# SAM4N_Xplained_Pro_EDBG.net
KiCad netlist of a schematic drawn in Altium Designer
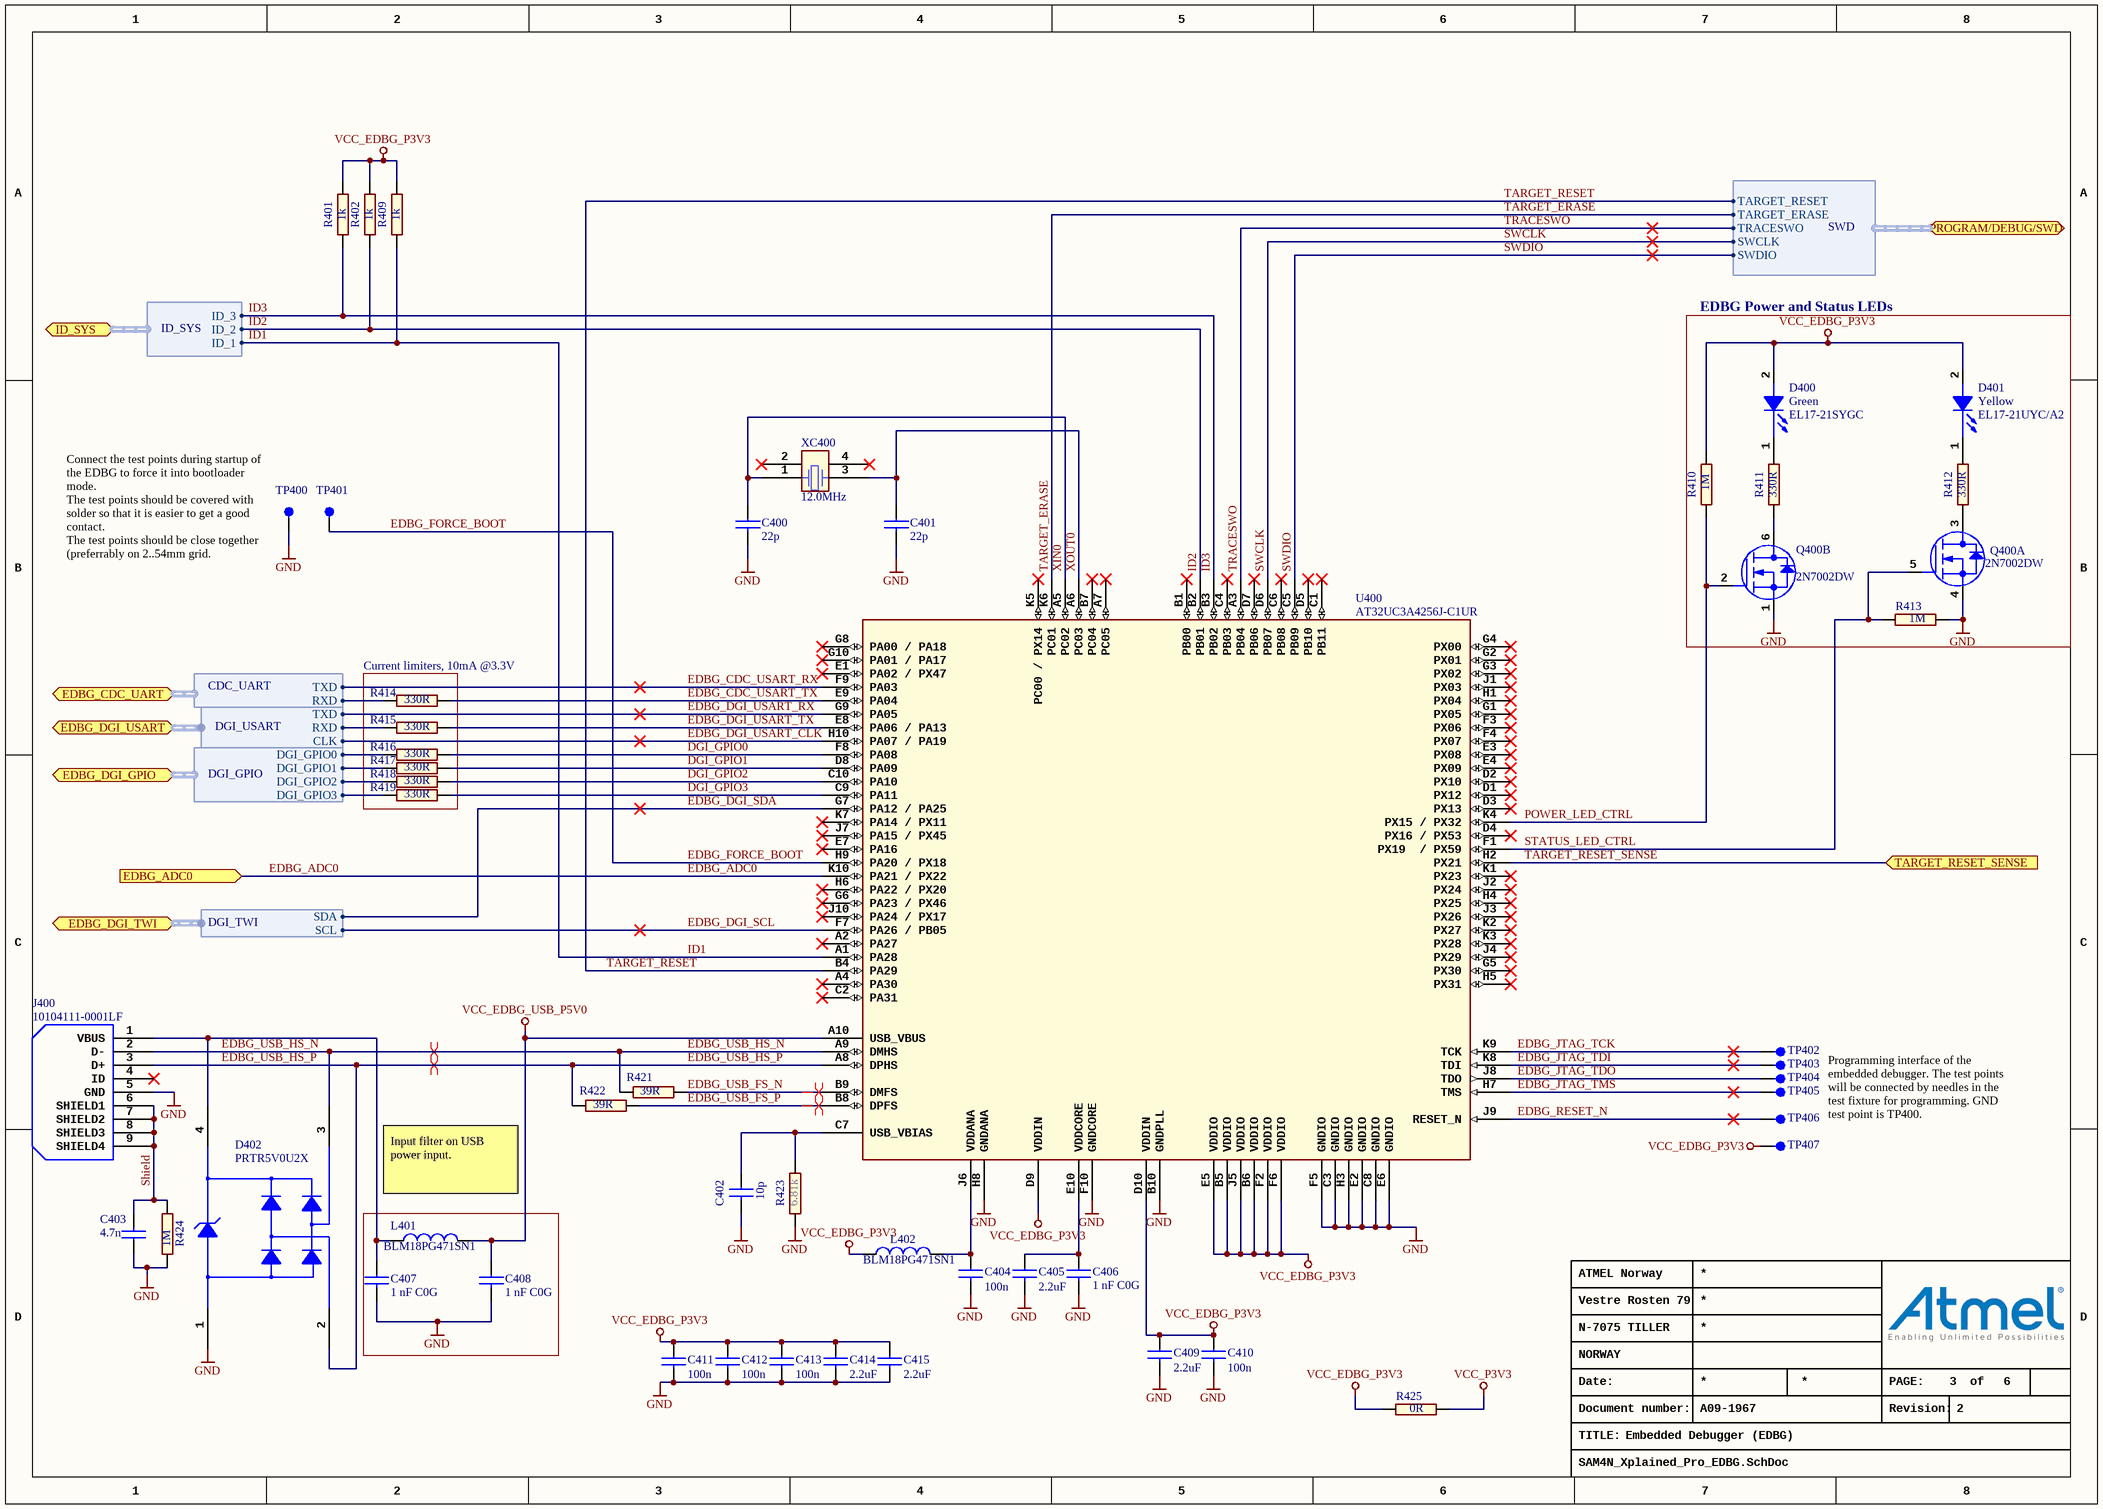
[diagram p0: SAM4N_Xplained_Pro_EDBG.SchDoc]

(export (version "E")
  (design (tool "Eeschema 10.0.6"))
  (components
    (comp (ref "C400")
      (value "22p")
      (footprint "AP1-00053")
      (description "Ceramic capacitor, SMD 0402, NP0, 50V, +/-5%")
      (fields (field (name "TOLERANCE") "50V, +/-5%"))
      (libsource (lib "AltiumDbLib") (part "CAP-NONPOL"))
    )
    (comp (ref "C401")
      (value "22p")
      (footprint "AP1-00053")
      (description "Ceramic capacitor, SMD 0402, NP0, 50V, +/-5%")
      (fields (field (name "TOLERANCE") "50V, +/-5%"))
      (libsource (lib "AltiumDbLib") (part "CAP-NONPOL"))
    )
    (comp (ref "C402")
      (value "10p")
      (footprint "AP1-00053")
      (description "Ceramic capacitor, SMD 0402, NP0, 50V, +/-5%")
      (fields (field (name "TOLERANCE") "50V, +/-5%"))
      (libsource (lib "AltiumDbLib") (part "CAP-NONPOL"))
    )
    (comp (ref "C403")
      (value "4.7n")
      (footprint "AP1-00053")
      (description "Ceramic capacitor, SMD 0402, X7R, 25V, +/-10%")
      (fields (field (name "TOLERANCE") "25V, +/-10%") (field (name "Comment") "CAP-NONPOL"))
      (libsource (lib "AltiumDbLib") (part "CAP-NONPOL"))
    )
    (comp (ref "C404")
      (value "100n")
      (footprint "AP1-00053")
      (description "Ceramic capacitor, SMD 0402, X7R, 16V, +/-10%")
      (fields (field (name "TOLERANCE") "16V, +/-10%") (field (name "MANUFACTURER") "Kemet"))
      (libsource (lib "AltiumDbLib") (part "CAP-NONPOL"))
    )
    (comp (ref "C405")
      (value "2.2uF")
      (footprint "AP1-00053")
      (description "Ceramic capacitor, SMD 0402, X5R, 6.3V, +/-20%")
      (fields (field (name "TOLERANCE") "±20%") (field (name "MANUFACTURER") "Kemet"))
      (libsource (lib "AltiumDbLib") (part "CAP-NONPOL"))
    )
    (comp (ref "C406")
      (value "1 nF C0G")
      (footprint "AP1-00053")
      (description "Ceramic capacitor, SMD 0402, C0G, 50V, +/-5%")
      (fields (field (name "TOLERANCE") "5%") (field (name "MANUFACTURER") "Murata"))
      (libsource (lib "AltiumDbLib") (part "CAP-NONPOL"))
    )
    (comp (ref "C407")
      (value "1 nF C0G")
      (footprint "AP1-00053")
      (description "Ceramic capacitor, SMD 0402, C0G, 50V, +/-5%")
      (fields (field (name "TOLERANCE") "5%") (field (name "MANUFACTURER") "Murata"))
      (libsource (lib "AltiumDbLib") (part "CAP-NONPOL"))
    )
    (comp (ref "C408")
      (value "1 nF C0G")
      (footprint "AP1-00053")
      (description "Ceramic capacitor, SMD 0402, C0G, 50V, +/-5%")
      (fields (field (name "TOLERANCE") "5%") (field (name "MANUFACTURER") "Murata"))
      (libsource (lib "AltiumDbLib") (part "CAP-NONPOL"))
    )
    (comp (ref "C409")
      (value "2.2uF")
      (footprint "AP1-00053")
      (description "Ceramic capacitor, SMD 0402, X5R, 6.3V, +/-20%")
      (fields (field (name "TOLERANCE") "±20%") (field (name "MANUFACTURER") "Kemet"))
      (libsource (lib "AltiumDbLib") (part "CAP-NONPOL"))
    )
    (comp (ref "C410")
      (value "100n")
      (footprint "AP1-00053")
      (description "Ceramic capacitor, SMD 0402, X7R, 16V, +/-10%")
      (fields (field (name "TOLERANCE") "16V, +/-10%") (field (name "MANUFACTURER") "Kemet"))
      (libsource (lib "AltiumDbLib") (part "CAP-NONPOL"))
    )
    (comp (ref "C411")
      (value "100n")
      (footprint "AP1-00053")
      (description "Ceramic capacitor, SMD 0402, X7R, 16V, +/-10%")
      (fields (field (name "TOLERANCE") "16V, +/-10%") (field (name "MANUFACTURER") "Kemet"))
      (libsource (lib "AltiumDbLib") (part "CAP-NONPOL"))
    )
    (comp (ref "C412")
      (value "100n")
      (footprint "AP1-00053")
      (description "Ceramic capacitor, SMD 0402, X7R, 16V, +/-10%")
      (fields (field (name "TOLERANCE") "16V, +/-10%") (field (name "MANUFACTURER") "Kemet"))
      (libsource (lib "AltiumDbLib") (part "CAP-NONPOL"))
    )
    (comp (ref "C413")
      (value "100n")
      (footprint "AP1-00053")
      (description "Ceramic capacitor, SMD 0402, X7R, 16V, +/-10%")
      (fields (field (name "TOLERANCE") "16V, +/-10%") (field (name "MANUFACTURER") "Kemet"))
      (libsource (lib "AltiumDbLib") (part "CAP-NONPOL"))
    )
    (comp (ref "C414")
      (value "2.2uF")
      (footprint "AP1-00053")
      (description "Ceramic capacitor, SMD 0402, X5R, 6.3V, +/-20%")
      (fields (field (name "TOLERANCE") "±20%") (field (name "MANUFACTURER") "Kemet"))
      (libsource (lib "AltiumDbLib") (part "CAP-NONPOL"))
    )
    (comp (ref "C415")
      (value "2.2uF")
      (footprint "AP1-00053")
      (description "Ceramic capacitor, SMD 0402, X5R, 6.3V, +/-20%")
      (fields (field (name "TOLERANCE") "±20%") (field (name "MANUFACTURER") "Kemet"))
      (libsource (lib "AltiumDbLib") (part "CAP-NONPOL"))
    )
    (comp (ref "D400")
      (value "Green")
      (footprint "AP4-00013")
      (description "LED, Green, Wave length=575nm, SMD 0805, ±70°")
      (fields
        (field (name "ALTIUM_VALUE") "EL17-21SYGC")
        (field (name "MANUFACTURER") "Everlight")
        (field (name "MPN") "EL17-21SYGC")
      )
      (libsource (lib "AltiumDbLib") (part "LED_12"))
    )
    (comp (ref "D401")
      (value "Yellow")
      (footprint "AP4-00013")
      (description "LED, Yellow, Wave length=591nm, SMD 0805, ±70°")
      (fields
        (field (name "ALTIUM_VALUE") "EL17-21UYC/A2")
        (field (name "MANUFACTURER") "Everlight")
        (field (name "MPN") "17-21UYC/S530-A3/TR8")
      )
      (libsource (lib "AltiumDbLib") (part "LED_12"))
    )
    (comp (ref "D402")
      (value "PRTR5V0U2X")
      (footprint "AP4-00001")
      (description "Double rail-to-rail USB ESD protection diode")
      (fields (field (name "MANUFACTURER") "Philips"))
      (libsource (lib "AltiumDbLib") (part "PRTR5V0U2X"))
    )
    (comp (ref "J400")
      (value "10104111-0001LF")
      (footprint "AP8-00604")
      (description "Micro USB AB Connector")
      (fields (field (name "MANUFACTURER") "FCI") (field (name "Comment") "USB_AB"))
      (libsource (lib "AltiumDbLib") (part "USB_AB"))
    )
    (comp (ref "L401")
      (value "BLM18PG471SN1")
      (footprint "AP3-00005")
      (description "SMD RF inductor 0603. Z=470Ohm (@100MHz), Max R(dc)=0.65Ohm, Max current=1A")
      (fields (field (name "TOLERANCE") "±25%") (field (name "MANUFACTURER") "Murata"))
      (libsource (lib "AltiumDbLib") (part "INDUCTOR"))
    )
    (comp (ref "L402")
      (value "BLM18PG471SN1")
      (footprint "AP3-00005")
      (description "SMD RF inductor 0603. Z=470Ohm (@100MHz), Max R(dc)=0.65Ohm, Max current=1A")
      (fields (field (name "TOLERANCE") "±25%") (field (name "MANUFACTURER") "Murata"))
      (libsource (lib "AltiumDbLib") (part "INDUCTOR"))
    )
    (comp (ref "Q400")
      (value "2N7002DW")
      (footprint "AP5-00001")
      (description "Dual N-Channel MOSFET, 60V, 115mA cont,RDS(ON) < 7.5 Ohm @50mA@5V, SOT-363")
      (fields
        (field (name "MANUFACTURER") "Fairchild")
        (field (name "Comment") "Same as 2N7002 but with two MOSFETs in one package")
      )
      (libsource (lib "AltiumDbLib") (part "MOSFET_DUAL_N_S2G2D1S1G1D2"))
    )
    (comp (ref "R401")
      (value "1k")
      (footprint "AP2-00000")
      (description "Thick film resistor, SMD 0402, 1/16W, 1%")
      (fields (field (name "TOLERANCE") "1 %") (field (name "Comment") "R2"))
      (libsource (lib "AltiumDbLib") (part "R2"))
    )
    (comp (ref "R402")
      (value "1k")
      (footprint "AP2-00000")
      (description "Thick film resistor, SMD 0402, 1/16W, 1%")
      (fields (field (name "TOLERANCE") "1 %") (field (name "Comment") "R2"))
      (libsource (lib "AltiumDbLib") (part "R2"))
    )
    (comp (ref "R409")
      (value "1k")
      (footprint "AP2-00000")
      (description "Thick film resistor, SMD 0402, 1/16W, 1%")
      (fields (field (name "TOLERANCE") "1 %") (field (name "Comment") "R2"))
      (libsource (lib "AltiumDbLib") (part "R2"))
    )
    (comp (ref "R410")
      (value "1M")
      (footprint "AP2-00000")
      (description "Thick film resistor, SMD 0402, 1/16W, 1%")
      (fields (field (name "TOLERANCE") "1 %") (field (name "MANUFACTURER") "KOA"))
      (libsource (lib "AltiumDbLib") (part "R2"))
    )
    (comp (ref "R411")
      (value "330R")
      (footprint "AP2-00000")
      (description "Thick film resistor, SMD 0402, 1/16W, 1%")
      (fields (field (name "TOLERANCE") "1 %") (field (name "Comment") "R2"))
      (libsource (lib "AltiumDbLib") (part "R2"))
    )
    (comp (ref "R412")
      (value "330R")
      (footprint "AP2-00000")
      (description "Thick film resistor, SMD 0402, 1/16W, 1%")
      (fields (field (name "TOLERANCE") "1 %") (field (name "Comment") "R2"))
      (libsource (lib "AltiumDbLib") (part "R2"))
    )
    (comp (ref "R413")
      (value "1M")
      (footprint "AP2-00000")
      (description "Thick film resistor, SMD 0402, 1/16W, 1%")
      (fields (field (name "TOLERANCE") "1 %") (field (name "MANUFACTURER") "KOA"))
      (libsource (lib "") (part "R2_3"))
    )
    (comp (ref "R414")
      (value "330R")
      (footprint "AP2-00000")
      (description "Thick film resistor, SMD 0402, 1/16W, 1%")
      (fields (field (name "TOLERANCE") "1 %") (field (name "Comment") "R2"))
      (libsource (lib "") (part "R2_1"))
    )
    (comp (ref "R415")
      (value "330R")
      (footprint "AP2-00000")
      (description "Thick film resistor, SMD 0402, 1/16W, 1%")
      (fields (field (name "TOLERANCE") "1 %") (field (name "Comment") "R2"))
      (libsource (lib "") (part "R2_1"))
    )
    (comp (ref "R416")
      (value "330R")
      (footprint "AP2-00000")
      (description "Thick film resistor, SMD 0402, 1/16W, 1%")
      (fields (field (name "TOLERANCE") "1 %") (field (name "Comment") "R2"))
      (libsource (lib "") (part "R2_1"))
    )
    (comp (ref "R417")
      (value "330R")
      (footprint "AP2-00000")
      (description "Thick film resistor, SMD 0402, 1/16W, 1%")
      (fields (field (name "TOLERANCE") "1 %") (field (name "Comment") "R2"))
      (libsource (lib "") (part "R2_1"))
    )
    (comp (ref "R418")
      (value "330R")
      (footprint "AP2-00000")
      (description "Thick film resistor, SMD 0402, 1/16W, 1%")
      (fields (field (name "TOLERANCE") "1 %") (field (name "Comment") "R2"))
      (libsource (lib "") (part "R2_1"))
    )
    (comp (ref "R419")
      (value "330R")
      (footprint "AP2-00000")
      (description "Thick film resistor, SMD 0402, 1/16W, 1%")
      (fields (field (name "TOLERANCE") "1 %") (field (name "Comment") "R2"))
      (libsource (lib "") (part "R2_1"))
    )
    (comp (ref "R421")
      (value "39R")
      (footprint "AP2-00011")
      (description "Thick film resistor, SMD 0402, 1/16W, 1%")
      (fields (field (name "TOLERANCE") "1 %") (field (name "Comment") "R2"))
      (libsource (lib "") (part "R2_2"))
    )
    (comp (ref "R422")
      (value "39R")
      (footprint "AP2-00011")
      (description "Thick film resistor, SMD 0402, 1/16W, 1%")
      (fields (field (name "TOLERANCE") "1 %") (field (name "Comment") "R2"))
      (libsource (lib "") (part "R2_2"))
    )
    (comp (ref "R423")
      (value "6.81k")
      (footprint "AP2-00011")
      (description "Thick film resistor, SMD 0402, 1/16W, 1%")
      (fields (field (name "TOLERANCE") "1%") (field (name "Comment") "R2"))
      (libsource (lib "AltiumDbLib") (part "R2"))
    )
    (comp (ref "R424")
      (value "1M")
      (footprint "AP2-00011")
      (description "Thick film resistor, SMD 0402, 1/16W, 1%")
      (fields (field (name "TOLERANCE") "1 %") (field (name "MANUFACTURER") "KOA"))
      (libsource (lib "") (part "R2_4"))
    )
    (comp (ref "R425")
      (value "0R")
      (footprint "AP2-00000")
      (description "Thick film resistor, SMD 0402, 1/16W, 1%")
      (fields (field (name "TOLERANCE") "1 %") (field (name "Comment") "R2"))
      (libsource (lib "") (part "R2_1"))
    )
    (comp (ref "TP400")
      (value "TESTPAD")
      (footprint "AP8-00010")
      (description "Single SMD testpad")
      (libsource (lib "AltiumDbLib") (part "TESTPOINT"))
    )
    (comp (ref "TP401")
      (value "TESTPAD")
      (footprint "AP8-00010")
      (description "Single SMD testpad")
      (libsource (lib "AltiumDbLib") (part "TESTPOINT"))
    )
    (comp (ref "TP402")
      (value "TESTPAD")
      (footprint "AP8-00010")
      (description "Single SMD testpad")
      (libsource (lib "AltiumDbLib") (part "TESTPOINT"))
    )
    (comp (ref "TP403")
      (value "TESTPAD")
      (footprint "AP8-00010")
      (description "Single SMD testpad")
      (libsource (lib "AltiumDbLib") (part "TESTPOINT"))
    )
    (comp (ref "TP404")
      (value "TESTPAD")
      (footprint "AP8-00010")
      (description "Single SMD testpad")
      (libsource (lib "AltiumDbLib") (part "TESTPOINT"))
    )
    (comp (ref "TP405")
      (value "TESTPAD")
      (footprint "AP8-00010")
      (description "Single SMD testpad")
      (libsource (lib "AltiumDbLib") (part "TESTPOINT"))
    )
    (comp (ref "TP406")
      (value "TESTPAD")
      (footprint "AP8-00010")
      (description "Single SMD testpad")
      (libsource (lib "AltiumDbLib") (part "TESTPOINT"))
    )
    (comp (ref "TP407")
      (value "TESTPAD")
      (footprint "AP8-00010")
      (description "Single SMD testpad")
      (libsource (lib "AltiumDbLib") (part "TESTPOINT"))
    )
    (comp (ref "U400")
      (value "AT32UC3A4256J-C1UR")
      (footprint "AP6-00206")
      (description "AVR 32-bit RISC MCU")
      (fields (field (name "MANUFACTURER") "ATMEL") (field (name "Comment") "100 ball VFBGA"))
      (libsource (lib "AltiumDbLib") (part "AT32UC3A4_VFBGA"))
    )
    (comp (ref "XC400")
      (value "12.0MHz")
      (footprint "AP7-00039")
      (description "Fox FQ5032B 12.0MHz SMD crystal 738B-12")
      (fields (field (name "TOLERANCE") "30PPM") (field (name "MANUFACTURER") "Fox  Electronics"))
      (libsource (lib "AltiumDbLib") (part "CRYSTAL1324"))
    )
  )
  (nets
    (net (code "7") (name "/DGI_GPIO0") (class "Default")
      (node (ref "R416") (pin "2") (pinfunction "2_2") (pintype "passive"))
      (node (ref "U400") (pin "F8") (pinfunction "PA08_F8") (pintype "bidirectional"))
    )
    (net (code "8") (name "/DGI_GPIO1") (class "Default")
      (node (ref "R417") (pin "2") (pinfunction "2_2") (pintype "passive"))
      (node (ref "U400") (pin "D8") (pinfunction "PA09_D8") (pintype "bidirectional"))
    )
    (net (code "9") (name "/DGI_GPIO2") (class "Default")
      (node (ref "R418") (pin "2") (pinfunction "2_2") (pintype "passive"))
      (node (ref "U400") (pin "C10") (pinfunction "PA10_C10") (pintype "bidirectional"))
    )
    (net (code "10") (name "/DGI_GPIO3") (class "Default")
      (node (ref "R419") (pin "2") (pinfunction "2_2") (pintype "passive"))
      (node (ref "U400") (pin "C9") (pinfunction "PA11_C9") (pintype "bidirectional"))
    )
    (net (code "11") (name "/EDBG_ADC0") (class "Default")
      (node (ref "U400") (pin "K10") (pinfunction "PA21_/_PX22_K10") (pintype "bidirectional"))
    )
    (net (code "13") (name "/EDBG_CDC_USART_RX") (class "Default")
      (node (ref "U400") (pin "F9") (pinfunction "PA03_F9") (pintype "bidirectional"))
    )
    (net (code "14") (name "/EDBG_CDC_USART_TX") (class "Default")
      (node (ref "R414") (pin "2") (pinfunction "2_2") (pintype "passive"))
      (node (ref "U400") (pin "E9") (pinfunction "PA04_E9") (pintype "bidirectional"))
    )
    (net (code "15") (name "/EDBG_DGI_SCL") (class "Default")
      (node (ref "U400") (pin "F7") (pinfunction "PA26_/_PB05_F7") (pintype "bidirectional"))
    )
    (net (code "16") (name "/EDBG_DGI_SDA") (class "Default")
      (node (ref "U400") (pin "G7") (pinfunction "PA12_/_PA25_G7") (pintype "bidirectional"))
    )
    (net (code "17") (name "/EDBG_DGI_USART_CLK") (class "Default")
      (node (ref "U400") (pin "H10") (pinfunction "PA07_/_PA19_H10") (pintype "bidirectional"))
    )
    (net (code "18") (name "/EDBG_DGI_USART_RX") (class "Default")
      (node (ref "U400") (pin "G9") (pinfunction "PA05_G9") (pintype "bidirectional"))
    )
    (net (code "19") (name "/EDBG_DGI_USART_TX") (class "Default")
      (node (ref "R415") (pin "2") (pinfunction "2_2") (pintype "passive"))
      (node (ref "U400") (pin "E8") (pinfunction "PA06_/_PA13_E8") (pintype "bidirectional"))
    )
    (net (code "21") (name "/EDBG_FORCE_BOOT") (class "Default")
      (node (ref "TP401") (pin "1") (pinfunction "1_1") (pintype "passive"))
      (node (ref "U400") (pin "H9") (pinfunction "PA20_/_PX18_H9") (pintype "bidirectional"))
    )
    (net (code "22") (name "/EDBG_JTAG_TCK") (class "Default")
      (node (ref "TP402") (pin "1") (pinfunction "1_1") (pintype "passive"))
      (node (ref "U400") (pin "K9") (pinfunction "TCK_K9") (pintype "input"))
    )
    (net (code "23") (name "/EDBG_JTAG_TDI") (class "Default")
      (node (ref "TP403") (pin "1") (pinfunction "1_1") (pintype "passive"))
      (node (ref "U400") (pin "K8") (pinfunction "TDI_K8") (pintype "input"))
    )
    (net (code "24") (name "/EDBG_JTAG_TDO") (class "Default")
      (node (ref "TP404") (pin "1") (pinfunction "1_1") (pintype "passive"))
      (node (ref "U400") (pin "J8") (pinfunction "TDO_J8") (pintype "output"))
    )
    (net (code "25") (name "/EDBG_JTAG_TMS") (class "Default")
      (node (ref "TP405") (pin "1") (pinfunction "1_1") (pintype "passive"))
      (node (ref "U400") (pin "H7") (pinfunction "TMS_H7") (pintype "input"))
    )
    (net (code "26") (name "/EDBG_RESET_N") (class "Default")
      (node (ref "TP406") (pin "1") (pinfunction "1_1") (pintype "passive"))
      (node (ref "U400") (pin "J9") (pinfunction "RESET_N_J9") (pintype "input"))
    )
    (net (code "27") (name "/EDBG_USB_FS_N") (class "Default")
      (node (ref "R421") (pin "2") (pinfunction "2_2") (pintype "passive"))
      (node (ref "U400") (pin "B9") (pinfunction "DMFS_B9") (pintype "bidirectional"))
    )
    (net (code "28") (name "/EDBG_USB_FS_P") (class "Default")
      (node (ref "R422") (pin "2") (pinfunction "2_2") (pintype "passive"))
      (node (ref "U400") (pin "B8") (pinfunction "DPFS_B8") (pintype "bidirectional"))
    )
    (net (code "29") (name "/EDBG_USB_HS_N") (class "Default")
      (node (ref "D402") (pin "3") (pinfunction "I/O_2_3") (pintype "passive"))
      (node (ref "J400") (pin "2") (pinfunction "D-_2") (pintype "passive"))
      (node (ref "R421") (pin "1") (pinfunction "1_1") (pintype "passive"))
      (node (ref "U400") (pin "A9") (pinfunction "DMHS_A9") (pintype "bidirectional"))
    )
    (net (code "30") (name "/EDBG_USB_HS_P") (class "Default")
      (node (ref "D402") (pin "2") (pinfunction "I/O_1_2") (pintype "passive"))
      (node (ref "J400") (pin "3") (pinfunction "D+_3") (pintype "passive"))
      (node (ref "R422") (pin "1") (pinfunction "1_1") (pintype "passive"))
      (node (ref "U400") (pin "A8") (pinfunction "DPHS_A8") (pintype "bidirectional"))
    )
    (net (code "31") (name "/ID1") (class "Default")
      (node (ref "R409") (pin "1") (pinfunction "1_1") (pintype "passive"))
      (node (ref "U400") (pin "A1") (pinfunction "PA28_A1") (pintype "bidirectional"))
    )
    (net (code "32") (name "/ID2") (class "Default")
      (node (ref "R402") (pin "1") (pinfunction "1_1") (pintype "passive"))
      (node (ref "U400") (pin "B2") (pinfunction "PB01_B2") (pintype "bidirectional"))
    )
    (net (code "33") (name "/ID3") (class "Default")
      (node (ref "R401") (pin "1") (pinfunction "1_1") (pintype "passive"))
      (node (ref "U400") (pin "B3") (pinfunction "PB02_B3") (pintype "bidirectional"))
    )
    (net (code "34") (name "/POWER_LED_CTRL") (class "Default")
      (node (ref "Q400") (pin "2") (pinfunction "G2_2") (pintype "passive"))
      (node (ref "R410") (pin "1") (pinfunction "1_1") (pintype "passive"))
      (node (ref "U400") (pin "K4") (pinfunction "PX15_/_PX32_K4") (pintype "bidirectional"))
    )
    (net (code "35") (name "/STATUS_LED_CTRL") (class "Default")
      (node (ref "Q400") (pin "5") (pinfunction "G1_5") (pintype "passive"))
      (node (ref "R413") (pin "2") (pinfunction "2_2") (pintype "passive"))
      (node (ref "U400") (pin "F1") (pinfunction "PX19__/_PX59_F1") (pintype "bidirectional"))
    )
    (net (code "36") (name "/SWCLK") (class "Default")
      (node (ref "U400") (pin "D6") (pinfunction "PB07_D6") (pintype "bidirectional"))
    )
    (net (code "37") (name "/SWDIO") (class "Default")
      (node (ref "U400") (pin "C5") (pinfunction "PB09_C5") (pintype "bidirectional"))
    )
    (net (code "38") (name "/Shield") (class "Default")
      (node (ref "C403") (pin "2") (pinfunction "2_2") (pintype "passive"))
      (node (ref "J400") (pin "6") (pinfunction "SHIELD1_6") (pintype "passive"))
      (node (ref "J400") (pin "7") (pinfunction "SHIELD2_7") (pintype "passive"))
      (node (ref "J400") (pin "8") (pinfunction "SHIELD3_8") (pintype "passive"))
      (node (ref "J400") (pin "9") (pinfunction "SHIELD4_9") (pintype "passive"))
      (node (ref "R424") (pin "2") (pinfunction "2_2") (pintype "passive"))
    )
    (net (code "39") (name "/TARGET_ERASE") (class "Default")
      (node (ref "U400") (pin "K6") (pinfunction "PC01_K6") (pintype "bidirectional"))
    )
    (net (code "40") (name "/TARGET_RESET") (class "Default")
      (node (ref "U400") (pin "B4") (pinfunction "PA29_B4") (pintype "bidirectional"))
    )
    (net (code "41") (name "/TARGET_RESET_SENSE") (class "Default")
      (node (ref "U400") (pin "H2") (pinfunction "PX21_H2") (pintype "bidirectional"))
    )
    (net (code "42") (name "/TRACESWO") (class "Default")
      (node (ref "U400") (pin "A3") (pinfunction "PB04_A3") (pintype "bidirectional"))
    )
    (net (code "43") (name "/XIN0") (class "Default")
      (node (ref "C400") (pin "1") (pinfunction "1_1") (pintype "passive"))
      (node (ref "U400") (pin "A5") (pinfunction "PC02_A5") (pintype "bidirectional"))
      (node (ref "XC400") (pin "1") (pinfunction "1_1") (pintype "passive"))
    )
    (net (code "44") (name "/XOUT0") (class "Default")
      (node (ref "C401") (pin "1") (pinfunction "1_1") (pintype "passive"))
      (node (ref "U400") (pin "A6") (pinfunction "PC03_A6") (pintype "bidirectional"))
      (node (ref "XC400") (pin "3") (pinfunction "3_3") (pintype "passive"))
    )
    (net (code "49") (name "GND") (class "Default")
      (node (ref "C400") (pin "2") (pinfunction "2_2") (pintype "passive"))
      (node (ref "C401") (pin "2") (pinfunction "2_2") (pintype "passive"))
      (node (ref "C402") (pin "2") (pinfunction "2_2") (pintype "passive"))
      (node (ref "C403") (pin "1") (pinfunction "1_1") (pintype "passive"))
      (node (ref "C404") (pin "2") (pinfunction "2_2") (pintype "passive"))
      (node (ref "C405") (pin "2") (pinfunction "2_2") (pintype "passive"))
      (node (ref "C406") (pin "2") (pinfunction "2_2") (pintype "passive"))
      (node (ref "C407") (pin "2") (pinfunction "2_2") (pintype "passive"))
      (node (ref "C408") (pin "2") (pinfunction "2_2") (pintype "passive"))
      (node (ref "C409") (pin "2") (pinfunction "2_2") (pintype "passive"))
      (node (ref "C410") (pin "2") (pinfunction "2_2") (pintype "passive"))
      (node (ref "C411") (pin "2") (pinfunction "2_2") (pintype "passive"))
      (node (ref "C412") (pin "2") (pinfunction "2_2") (pintype "passive"))
      (node (ref "C413") (pin "2") (pinfunction "2_2") (pintype "passive"))
      (node (ref "C414") (pin "2") (pinfunction "2_2") (pintype "passive"))
      (node (ref "C415") (pin "2") (pinfunction "2_2") (pintype "passive"))
      (node (ref "D402") (pin "1") (pinfunction "GND_1") (pintype "passive"))
      (node (ref "J400") (pin "5") (pinfunction "GND_5") (pintype "passive"))
      (node (ref "Q400") (pin "1") (pinfunction "S2_1") (pintype "passive"))
      (node (ref "Q400") (pin "4") (pinfunction "S1_4") (pintype "passive"))
      (node (ref "R413") (pin "1") (pinfunction "1_1") (pintype "passive"))
      (node (ref "R423") (pin "1") (pinfunction "1_1") (pintype "passive"))
      (node (ref "R424") (pin "1") (pinfunction "1_1") (pintype "passive"))
      (node (ref "TP400") (pin "1") (pinfunction "1_1") (pintype "passive"))
      (node (ref "U400") (pin "B10") (pinfunction "GNDPLL_B10") (pintype "power_in"))
      (node (ref "U400") (pin "C3") (pinfunction "GNDIO_C3") (pintype "power_in"))
      (node (ref "U400") (pin "C8") (pinfunction "GNDIO_C8") (pintype "power_in"))
      (node (ref "U400") (pin "E2") (pinfunction "GNDIO_E2") (pintype "power_in"))
      (node (ref "U400") (pin "E6") (pinfunction "GNDIO_E6") (pintype "power_in"))
      (node (ref "U400") (pin "F10") (pinfunction "GNDCORE_F10") (pintype "power_in"))
      (node (ref "U400") (pin "F5") (pinfunction "GNDIO_F5") (pintype "power_in"))
      (node (ref "U400") (pin "H3") (pinfunction "GNDIO_H3") (pintype "power_in"))
      (node (ref "U400") (pin "H8") (pinfunction "GNDANA_H8") (pintype "power_in"))
    )
    (net (code "50") (name "Net-(D400-CATHODE)") (class "Default")
      (node (ref "D400") (pin "1") (pinfunction "CATHODE_1") (pintype "passive"))
      (node (ref "R411") (pin "2") (pinfunction "2_2") (pintype "passive"))
    )
    (net (code "51") (name "Net-(D401-CATHODE)") (class "Default")
      (node (ref "D401") (pin "1") (pinfunction "CATHODE_1") (pintype "passive"))
      (node (ref "R412") (pin "2") (pinfunction "2_2") (pintype "passive"))
    )
    (net (code "52") (name "Net-(D402-VCC)") (class "Default")
      (node (ref "C407") (pin "1") (pinfunction "1_1") (pintype "passive"))
      (node (ref "D402") (pin "4") (pinfunction "VCC_4") (pintype "passive"))
      (node (ref "J400") (pin "1") (pinfunction "VBUS_1") (pintype "passive"))
      (node (ref "L401") (pin "1") (pinfunction "1_1") (pintype "passive"))
    )
    (net (code "53") (name "Net-(Q400A-D1)") (class "Default")
      (node (ref "Q400") (pin "3") (pinfunction "D1_3") (pintype "passive"))
      (node (ref "R412") (pin "1") (pinfunction "1_1") (pintype "passive"))
    )
    (net (code "54") (name "Net-(Q400B-D2)") (class "Default")
      (node (ref "Q400") (pin "6") (pinfunction "D2_6") (pintype "passive"))
      (node (ref "R411") (pin "1") (pinfunction "1_1") (pintype "passive"))
    )
    (net (code "55") (name "Net-(U400-USB_VBIAS)") (class "Default")
      (node (ref "C402") (pin "1") (pinfunction "1_1") (pintype "passive"))
      (node (ref "R423") (pin "2") (pinfunction "2_2") (pintype "passive"))
      (node (ref "U400") (pin "C7") (pinfunction "USB_VBIAS_C7") (pintype "power_in"))
    )
    (net (code "56") (name "Net-(U400-VDDANA)") (class "Default")
      (node (ref "C404") (pin "1") (pinfunction "1_1") (pintype "passive"))
      (node (ref "L402") (pin "2") (pinfunction "2_2") (pintype "passive"))
      (node (ref "U400") (pin "J6") (pinfunction "VDDANA_J6") (pintype "power_in"))
    )
    (net (code "57") (name "Net-(U400-VDDCORE)") (class "Default")
      (node (ref "C405") (pin "1") (pinfunction "1_1") (pintype "passive"))
      (node (ref "C406") (pin "1") (pinfunction "1_1") (pintype "passive"))
      (node (ref "U400") (pin "E10") (pinfunction "VDDCORE_E10") (pintype "power_in"))
    )
    (net (code "58") (name "VCC_EDBG_P3V3") (class "Default")
      (node (ref "C409") (pin "1") (pinfunction "1_1") (pintype "passive"))
      (node (ref "C410") (pin "1") (pinfunction "1_1") (pintype "passive"))
      (node (ref "C411") (pin "1") (pinfunction "1_1") (pintype "passive"))
      (node (ref "C412") (pin "1") (pinfunction "1_1") (pintype "passive"))
      (node (ref "C413") (pin "1") (pinfunction "1_1") (pintype "passive"))
      (node (ref "C414") (pin "1") (pinfunction "1_1") (pintype "passive"))
      (node (ref "C415") (pin "1") (pinfunction "1_1") (pintype "passive"))
      (node (ref "D400") (pin "2") (pinfunction "ANODE_2") (pintype "passive"))
      (node (ref "D401") (pin "2") (pinfunction "ANODE_2") (pintype "passive"))
      (node (ref "L402") (pin "1") (pinfunction "1_1") (pintype "passive"))
      (node (ref "R401") (pin "2") (pinfunction "2_2") (pintype "passive"))
      (node (ref "R402") (pin "2") (pinfunction "2_2") (pintype "passive"))
      (node (ref "R409") (pin "2") (pinfunction "2_2") (pintype "passive"))
      (node (ref "R410") (pin "2") (pinfunction "2_2") (pintype "passive"))
      (node (ref "R425") (pin "1") (pinfunction "1_1") (pintype "passive"))
      (node (ref "TP407") (pin "1") (pinfunction "1_1") (pintype "passive"))
      (node (ref "U400") (pin "B5") (pinfunction "VDDIO_B5") (pintype "power_in"))
      (node (ref "U400") (pin "B6") (pinfunction "VDDIO_B6") (pintype "power_in"))
      (node (ref "U400") (pin "D10") (pinfunction "VDDIN_D10") (pintype "power_in"))
      (node (ref "U400") (pin "D9") (pinfunction "VDDIN_D9") (pintype "power_in"))
      (node (ref "U400") (pin "E5") (pinfunction "VDDIO_E5") (pintype "power_in"))
      (node (ref "U400") (pin "F2") (pinfunction "VDDIO_F2") (pintype "power_in"))
      (node (ref "U400") (pin "F6") (pinfunction "VDDIO_F6") (pintype "power_in"))
      (node (ref "U400") (pin "J5") (pinfunction "VDDIO_J5") (pintype "power_in"))
    )
    (net (code "59") (name "VCC_EDBG_USB_P5V0") (class "Default")
      (node (ref "C408") (pin "1") (pinfunction "1_1") (pintype "passive"))
      (node (ref "L401") (pin "2") (pinfunction "2_2") (pintype "passive"))
      (node (ref "U400") (pin "A10") (pinfunction "USB_VBUS_A10") (pintype "power_in"))
    )
    (net (code "60") (name "VCC_P3V3") (class "Default")
      (node (ref "R425") (pin "2") (pinfunction "2_2") (pintype "passive"))
    )
    (net (code "61") (name "unconnected-(J400-ID-Pad4)") (class "Default")
      (node (ref "J400") (pin "4") (pinfunction "ID_4") (pintype "passive+no_connect"))
    )
    (net (code "62") (name "unconnected-(R414-Pad1)") (class "Default")
      (node (ref "R414") (pin "1") (pinfunction "1_1") (pintype "passive"))
    )
    (net (code "63") (name "unconnected-(R415-Pad1)") (class "Default")
      (node (ref "R415") (pin "1") (pinfunction "1_1") (pintype "passive"))
    )
    (net (code "64") (name "unconnected-(R416-Pad1)") (class "Default")
      (node (ref "R416") (pin "1") (pinfunction "1_1") (pintype "passive"))
    )
    (net (code "65") (name "unconnected-(R417-Pad1)") (class "Default")
      (node (ref "R417") (pin "1") (pinfunction "1_1") (pintype "passive"))
    )
    (net (code "66") (name "unconnected-(R418-Pad1)") (class "Default")
      (node (ref "R418") (pin "1") (pinfunction "1_1") (pintype "passive"))
    )
    (net (code "67") (name "unconnected-(R419-Pad1)") (class "Default")
      (node (ref "R419") (pin "1") (pinfunction "1_1") (pintype "passive"))
    )
    (net (code "68") (name "unconnected-(U400-PA00_{slash}_PA18-PadG8)") (class "Default")
      (node (ref "U400") (pin "G8") (pinfunction "PA00_/_PA18_G8") (pintype "bidirectional+no_connect"))
    )
    (net (code "69") (name "unconnected-(U400-PA01_{slash}_PA17-PadG10)") (class "Default")
      (node (ref "U400") (pin "G10") (pinfunction "PA01_/_PA17_G10") (pintype "bidirectional+no_connect"))
    )
    (net (code "70") (name "unconnected-(U400-PA02_{slash}_PX47-PadE1)") (class "Default")
      (node (ref "U400") (pin "E1") (pinfunction "PA02_/_PX47_E1") (pintype "bidirectional+no_connect"))
    )
    (net (code "71") (name "unconnected-(U400-PA14_{slash}_PX11-PadK7)") (class "Default")
      (node (ref "U400") (pin "K7") (pinfunction "PA14_/_PX11_K7") (pintype "bidirectional+no_connect"))
    )
    (net (code "72") (name "unconnected-(U400-PA15_{slash}_PX45-PadJ7)") (class "Default")
      (node (ref "U400") (pin "J7") (pinfunction "PA15_/_PX45_J7") (pintype "bidirectional+no_connect"))
    )
    (net (code "73") (name "unconnected-(U400-PA16-PadE7)") (class "Default")
      (node (ref "U400") (pin "E7") (pinfunction "PA16_E7") (pintype "bidirectional+no_connect"))
    )
    (net (code "74") (name "unconnected-(U400-PA22_{slash}_PX20-PadH6)") (class "Default")
      (node (ref "U400") (pin "H6") (pinfunction "PA22_/_PX20_H6") (pintype "bidirectional+no_connect"))
    )
    (net (code "75") (name "unconnected-(U400-PA23_{slash}_PX46-PadG6)") (class "Default")
      (node (ref "U400") (pin "G6") (pinfunction "PA23_/_PX46_G6") (pintype "bidirectional+no_connect"))
    )
    (net (code "76") (name "unconnected-(U400-PA24_{slash}_PX17-PadJ10)") (class "Default")
      (node (ref "U400") (pin "J10") (pinfunction "PA24_/_PX17_J10") (pintype "bidirectional+no_connect"))
    )
    (net (code "77") (name "unconnected-(U400-PA27-PadA2)") (class "Default")
      (node (ref "U400") (pin "A2") (pinfunction "PA27_A2") (pintype "bidirectional+no_connect"))
    )
    (net (code "78") (name "unconnected-(U400-PA30-PadA4)") (class "Default")
      (node (ref "U400") (pin "A4") (pinfunction "PA30_A4") (pintype "bidirectional+no_connect"))
    )
    (net (code "79") (name "unconnected-(U400-PA31-PadC2)") (class "Default")
      (node (ref "U400") (pin "C2") (pinfunction "PA31_C2") (pintype "bidirectional+no_connect"))
    )
    (net (code "80") (name "unconnected-(U400-PB00-PadB1)") (class "Default")
      (node (ref "U400") (pin "B1") (pinfunction "PB00_B1") (pintype "bidirectional+no_connect"))
    )
    (net (code "81") (name "unconnected-(U400-PB03-PadC4)") (class "Default")
      (node (ref "U400") (pin "C4") (pinfunction "PB03_C4") (pintype "bidirectional+no_connect"))
    )
    (net (code "82") (name "unconnected-(U400-PB06-PadD7)") (class "Default")
      (node (ref "U400") (pin "D7") (pinfunction "PB06_D7") (pintype "bidirectional+no_connect"))
    )
    (net (code "83") (name "unconnected-(U400-PB08-PadC6)") (class "Default")
      (node (ref "U400") (pin "C6") (pinfunction "PB08_C6") (pintype "bidirectional+no_connect"))
    )
    (net (code "84") (name "unconnected-(U400-PB10-PadD5)") (class "Default")
      (node (ref "U400") (pin "D5") (pinfunction "PB10_D5") (pintype "bidirectional+no_connect"))
    )
    (net (code "85") (name "unconnected-(U400-PB11-PadC1)") (class "Default")
      (node (ref "U400") (pin "C1") (pinfunction "PB11_C1") (pintype "bidirectional+no_connect"))
    )
    (net (code "86") (name "unconnected-(U400-PC00_{slash}_PX14-PadK5)") (class "Default")
      (node (ref "U400") (pin "K5") (pinfunction "PC00_/_PX14_K5") (pintype "bidirectional+no_connect"))
    )
    (net (code "87") (name "unconnected-(U400-PC04-PadB7)") (class "Default")
      (node (ref "U400") (pin "B7") (pinfunction "PC04_B7") (pintype "bidirectional+no_connect"))
    )
    (net (code "88") (name "unconnected-(U400-PC05-PadA7)") (class "Default")
      (node (ref "U400") (pin "A7") (pinfunction "PC05_A7") (pintype "bidirectional+no_connect"))
    )
    (net (code "89") (name "unconnected-(U400-PX00-PadG4)") (class "Default")
      (node (ref "U400") (pin "G4") (pinfunction "PX00_G4") (pintype "bidirectional+no_connect"))
    )
    (net (code "90") (name "unconnected-(U400-PX01-PadG2)") (class "Default")
      (node (ref "U400") (pin "G2") (pinfunction "PX01_G2") (pintype "bidirectional+no_connect"))
    )
    (net (code "91") (name "unconnected-(U400-PX02-PadG3)") (class "Default")
      (node (ref "U400") (pin "G3") (pinfunction "PX02_G3") (pintype "bidirectional+no_connect"))
    )
    (net (code "92") (name "unconnected-(U400-PX03-PadJ1)") (class "Default")
      (node (ref "U400") (pin "J1") (pinfunction "PX03_J1") (pintype "bidirectional+no_connect"))
    )
    (net (code "93") (name "unconnected-(U400-PX04-PadH1)") (class "Default")
      (node (ref "U400") (pin "H1") (pinfunction "PX04_H1") (pintype "bidirectional+no_connect"))
    )
    (net (code "94") (name "unconnected-(U400-PX05-PadG1)") (class "Default")
      (node (ref "U400") (pin "G1") (pinfunction "PX05_G1") (pintype "bidirectional+no_connect"))
    )
    (net (code "95") (name "unconnected-(U400-PX06-PadF3)") (class "Default")
      (node (ref "U400") (pin "F3") (pinfunction "PX06_F3") (pintype "bidirectional+no_connect"))
    )
    (net (code "96") (name "unconnected-(U400-PX07-PadF4)") (class "Default")
      (node (ref "U400") (pin "F4") (pinfunction "PX07_F4") (pintype "bidirectional+no_connect"))
    )
    (net (code "97") (name "unconnected-(U400-PX08-PadE3)") (class "Default")
      (node (ref "U400") (pin "E3") (pinfunction "PX08_E3") (pintype "bidirectional+no_connect"))
    )
    (net (code "98") (name "unconnected-(U400-PX09-PadE4)") (class "Default")
      (node (ref "U400") (pin "E4") (pinfunction "PX09_E4") (pintype "bidirectional+no_connect"))
    )
    (net (code "99") (name "unconnected-(U400-PX10-PadD2)") (class "Default")
      (node (ref "U400") (pin "D2") (pinfunction "PX10_D2") (pintype "bidirectional+no_connect"))
    )
    (net (code "100") (name "unconnected-(U400-PX12-PadD1)") (class "Default")
      (node (ref "U400") (pin "D1") (pinfunction "PX12_D1") (pintype "bidirectional+no_connect"))
    )
    (net (code "101") (name "unconnected-(U400-PX13-PadD3)") (class "Default")
      (node (ref "U400") (pin "D3") (pinfunction "PX13_D3") (pintype "bidirectional+no_connect"))
    )
    (net (code "102") (name "unconnected-(U400-PX16_{slash}_PX53-PadD4)") (class "Default")
      (node (ref "U400") (pin "D4") (pinfunction "PX16_/_PX53_D4") (pintype "bidirectional+no_connect"))
    )
    (net (code "103") (name "unconnected-(U400-PX23-PadK1)") (class "Default")
      (node (ref "U400") (pin "K1") (pinfunction "PX23_K1") (pintype "bidirectional+no_connect"))
    )
    (net (code "104") (name "unconnected-(U400-PX24-PadJ2)") (class "Default")
      (node (ref "U400") (pin "J2") (pinfunction "PX24_J2") (pintype "bidirectional+no_connect"))
    )
    (net (code "105") (name "unconnected-(U400-PX25-PadH4)") (class "Default")
      (node (ref "U400") (pin "H4") (pinfunction "PX25_H4") (pintype "bidirectional+no_connect"))
    )
    (net (code "106") (name "unconnected-(U400-PX26-PadJ3)") (class "Default")
      (node (ref "U400") (pin "J3") (pinfunction "PX26_J3") (pintype "bidirectional+no_connect"))
    )
    (net (code "107") (name "unconnected-(U400-PX27-PadK2)") (class "Default")
      (node (ref "U400") (pin "K2") (pinfunction "PX27_K2") (pintype "bidirectional+no_connect"))
    )
    (net (code "108") (name "unconnected-(U400-PX28-PadK3)") (class "Default")
      (node (ref "U400") (pin "K3") (pinfunction "PX28_K3") (pintype "bidirectional+no_connect"))
    )
    (net (code "109") (name "unconnected-(U400-PX29-PadJ4)") (class "Default")
      (node (ref "U400") (pin "J4") (pinfunction "PX29_J4") (pintype "bidirectional+no_connect"))
    )
    (net (code "110") (name "unconnected-(U400-PX30-PadG5)") (class "Default")
      (node (ref "U400") (pin "G5") (pinfunction "PX30_G5") (pintype "bidirectional+no_connect"))
    )
    (net (code "111") (name "unconnected-(U400-PX31-PadH5)") (class "Default")
      (node (ref "U400") (pin "H5") (pinfunction "PX31_H5") (pintype "bidirectional+no_connect"))
    )
    (net (code "112") (name "unconnected-(XC400-Pad2)") (class "Default")
      (node (ref "XC400") (pin "2") (pinfunction "2_2") (pintype "passive+no_connect"))
    )
    (net (code "113") (name "unconnected-(XC400-Pad4)") (class "Default")
      (node (ref "XC400") (pin "4") (pinfunction "4_4") (pintype "passive+no_connect"))
    )
  )
)
